# MICROSD_CARD_update.net
KiCad netlist of a schematic drawn in Altium Designer
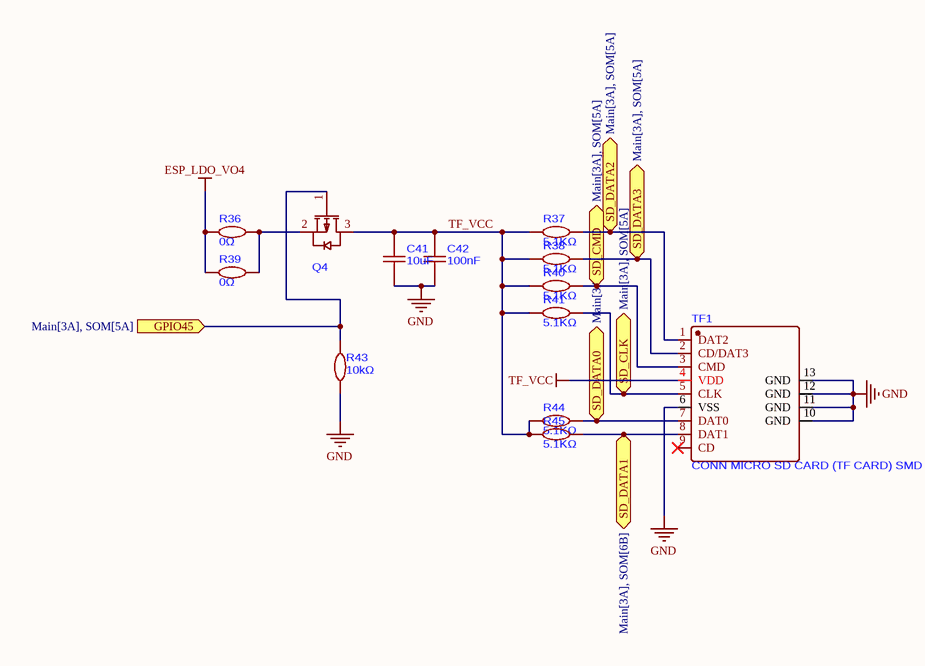
[diagram p0: MICROSD CARD_update.SchDoc]

(export (version "E")
  (design (tool "Eeschema 10.0.6"))
  (components
    (comp (ref "C41")
      (value "10uF")
      (footprint "C0603")
      (description "25V 10uF X5R ±20% 0603 Ceramic Capacitors ROHS")
      (libsource (lib "Schlib2") (part "CL10A106MA8NRNC"))
    )
    (comp (ref "C42")
      (value "100nF")
      (footprint "C0603")
      (description "50V 100nF X7R ±10% 0603 Ceramic Capacitors ROHS")
      (libsource (lib "Schlib2") (part "CC0603KRX7R9BB104"))
    )
    (comp (ref "Q4")
      (value "MOSFET P-CH 30V 4.3A SOT-23")
      (footprint "SOT-23-3_L2.9-W1.6-P1.90-LS2.8-BR")
      (description "30V 4.3A 48mΩ@10V 2.5V@250uA 1 P-Channel SOT-23 Single FETs, MOSFETs ROHS")
      (libsource (lib "Schlib2") (part "AO3407A"))
    )
    (comp (ref "R36")
      (value "0Ω")
      (footprint "R0603")
      (description "100mW 0Ω 75V Thick Film Resistor ±5% 0603 Chip Resistor - Surface Mount RoHS")
      (libsource (lib "Schlib2") (part "RC0603JR-070RL"))
    )
    (comp (ref "R37")
      (value "5.1KΩ")
      (footprint "R0603")
      (description "100mW 5.1kΩ 75V ±100ppm/℃ Thick Film Resistor ±1% 0603 Chip Resistor - Surface Mount RoHS")
      (libsource (lib "Schlib2") (part "FRC0603F5101TS"))
    )
    (comp (ref "R38")
      (value "5.1KΩ")
      (footprint "R0603")
      (description "100mW 5.1kΩ 75V ±100ppm/℃ Thick Film Resistor ±1% 0603 Chip Resistor - Surface Mount RoHS")
      (libsource (lib "Schlib2") (part "FRC0603F5101TS"))
    )
    (comp (ref "R39")
      (value "0Ω")
      (footprint "R0603")
      (description "100mW 0Ω 75V Thick Film Resistor ±5% 0603 Chip Resistor - Surface Mount RoHS")
      (libsource (lib "Schlib2") (part "RC0603JR-070RL"))
    )
    (comp (ref "R40")
      (value "5.1KΩ")
      (footprint "R0603")
      (description "100mW 5.1kΩ 75V ±100ppm/℃ Thick Film Resistor ±1% 0603 Chip Resistor - Surface Mount RoHS")
      (libsource (lib "Schlib2") (part "FRC0603F5101TS"))
    )
    (comp (ref "R41")
      (value "5.1KΩ")
      (footprint "R0603")
      (description "100mW 5.1kΩ 75V ±100ppm/℃ Thick Film Resistor ±1% 0603 Chip Resistor - Surface Mount RoHS")
      (libsource (lib "Schlib2") (part "FRC0603F5101TS"))
    )
    (comp (ref "R43")
      (value "10kΩ")
      (footprint "R0603")
      (description "100mW 10kΩ 75V ±100ppm/℃ Thick Film Resistor ±1% 0603 Chip Resistor - Surface Mount ROHS")
      (libsource (lib "Schlib2") (part "RC0603FR-0710KL"))
    )
    (comp (ref "R44")
      (value "5.1KΩ")
      (footprint "R0603")
      (description "100mW 5.1kΩ 75V ±100ppm/℃ Thick Film Resistor ±1% 0603 Chip Resistor - Surface Mount RoHS")
      (libsource (lib "Schlib2") (part "FRC0603F5101TS"))
    )
    (comp (ref "R45")
      (value "5.1KΩ")
      (footprint "R0603")
      (description "100mW 5.1kΩ 75V ±100ppm/℃ Thick Film Resistor ±1% 0603 Chip Resistor - Surface Mount RoHS")
      (libsource (lib "Schlib2") (part "FRC0603F5101TS"))
    )
    (comp (ref "TF1")
      (value "CONN MICRO SD CARD (TF CARD) SMD")
      (footprint "TF-SMD_SH_SH-TF-01A")
      (description "-25℃~+85℃ Push-Push 2mm Connector and Ejector MicroSD Card (TF Card) SMD PC Card Sockets RoHS")
      (libsource (lib "Schlib2") (part "SH-TF-01A"))
    )
  )
  (nets
    (net (code "1") (name "/GPIO45") (class "Default")
      (node (ref "Q4") (pin "1") (pinfunction "G_1") (pintype "passive"))
      (node (ref "R43") (pin "2") (pinfunction "2_2") (pintype "passive"))
    )
    (net (code "2") (name "/SD_CLK") (class "Default")
      (node (ref "R41") (pin "2") (pinfunction "2_2") (pintype "passive"))
      (node (ref "TF1") (pin "5") (pinfunction "CLK_5") (pintype "passive"))
    )
    (net (code "3") (name "/SD_CMD") (class "Default")
      (node (ref "R40") (pin "2") (pinfunction "2_2") (pintype "passive"))
      (node (ref "TF1") (pin "3") (pinfunction "CMD_3") (pintype "passive"))
    )
    (net (code "4") (name "/SD_DATA0") (class "Default")
      (node (ref "R44") (pin "2") (pinfunction "2_2") (pintype "passive"))
      (node (ref "TF1") (pin "7") (pinfunction "DAT0_7") (pintype "passive"))
    )
    (net (code "5") (name "/SD_DATA1") (class "Default")
      (node (ref "R45") (pin "2") (pinfunction "2_2") (pintype "passive"))
      (node (ref "TF1") (pin "8") (pinfunction "DAT1_8") (pintype "passive"))
    )
    (net (code "6") (name "/SD_DATA2") (class "Default")
      (node (ref "R37") (pin "2") (pinfunction "2_2") (pintype "passive"))
      (node (ref "TF1") (pin "1") (pinfunction "DAT2_1") (pintype "passive"))
    )
    (net (code "7") (name "/SD_DATA3") (class "Default")
      (node (ref "R38") (pin "2") (pinfunction "2_2") (pintype "passive"))
      (node (ref "TF1") (pin "2") (pinfunction "CD/DAT3_2") (pintype "passive"))
    )
    (net (code "8") (name "ESP_LDO_VO4") (class "Default")
      (node (ref "R36") (pin "1") (pinfunction "1_1") (pintype "passive"))
      (node (ref "R39") (pin "1") (pinfunction "1_1") (pintype "passive"))
    )
    (net (code "9") (name "GND") (class "Default")
      (node (ref "C41") (pin "1") (pinfunction "1_1") (pintype "passive"))
      (node (ref "C42") (pin "1") (pinfunction "1_1") (pintype "passive"))
      (node (ref "R43") (pin "1") (pinfunction "1_1") (pintype "passive"))
      (node (ref "TF1") (pin "10") (pinfunction "GND_10") (pintype "passive"))
      (node (ref "TF1") (pin "11") (pinfunction "GND_11") (pintype "passive"))
      (node (ref "TF1") (pin "12") (pinfunction "GND_12") (pintype "passive"))
      (node (ref "TF1") (pin "13") (pinfunction "GND_13") (pintype "passive"))
      (node (ref "TF1") (pin "6") (pinfunction "VSS_6") (pintype "passive"))
    )
    (net (code "10") (name "Net-(Q4-S)") (class "Default")
      (node (ref "Q4") (pin "2") (pinfunction "S_2") (pintype "passive"))
      (node (ref "R36") (pin "2") (pinfunction "2_2") (pintype "passive"))
      (node (ref "R39") (pin "2") (pinfunction "2_2") (pintype "passive"))
    )
    (net (code "11") (name "TF_VCC") (class "Default")
      (node (ref "C41") (pin "2") (pinfunction "2_2") (pintype "passive"))
      (node (ref "C42") (pin "2") (pinfunction "2_2") (pintype "passive"))
      (node (ref "Q4") (pin "3") (pinfunction "D_3") (pintype "passive"))
      (node (ref "R37") (pin "1") (pinfunction "1_1") (pintype "passive"))
      (node (ref "R38") (pin "1") (pinfunction "1_1") (pintype "passive"))
      (node (ref "R40") (pin "1") (pinfunction "1_1") (pintype "passive"))
      (node (ref "R41") (pin "1") (pinfunction "1_1") (pintype "passive"))
      (node (ref "R44") (pin "1") (pinfunction "1_1") (pintype "passive"))
      (node (ref "R45") (pin "1") (pinfunction "1_1") (pintype "passive"))
      (node (ref "TF1") (pin "4") (pinfunction "VDD_4") (pintype "passive"))
    )
    (net (code "12") (name "unconnected-(TF1-CD-Pad9)") (class "Default")
      (node (ref "TF1") (pin "9") (pinfunction "CD_9") (pintype "passive+no_connect"))
    )
  )
)
